# W5500.net
KiCad netlist of a schematic drawn in Altium Designer
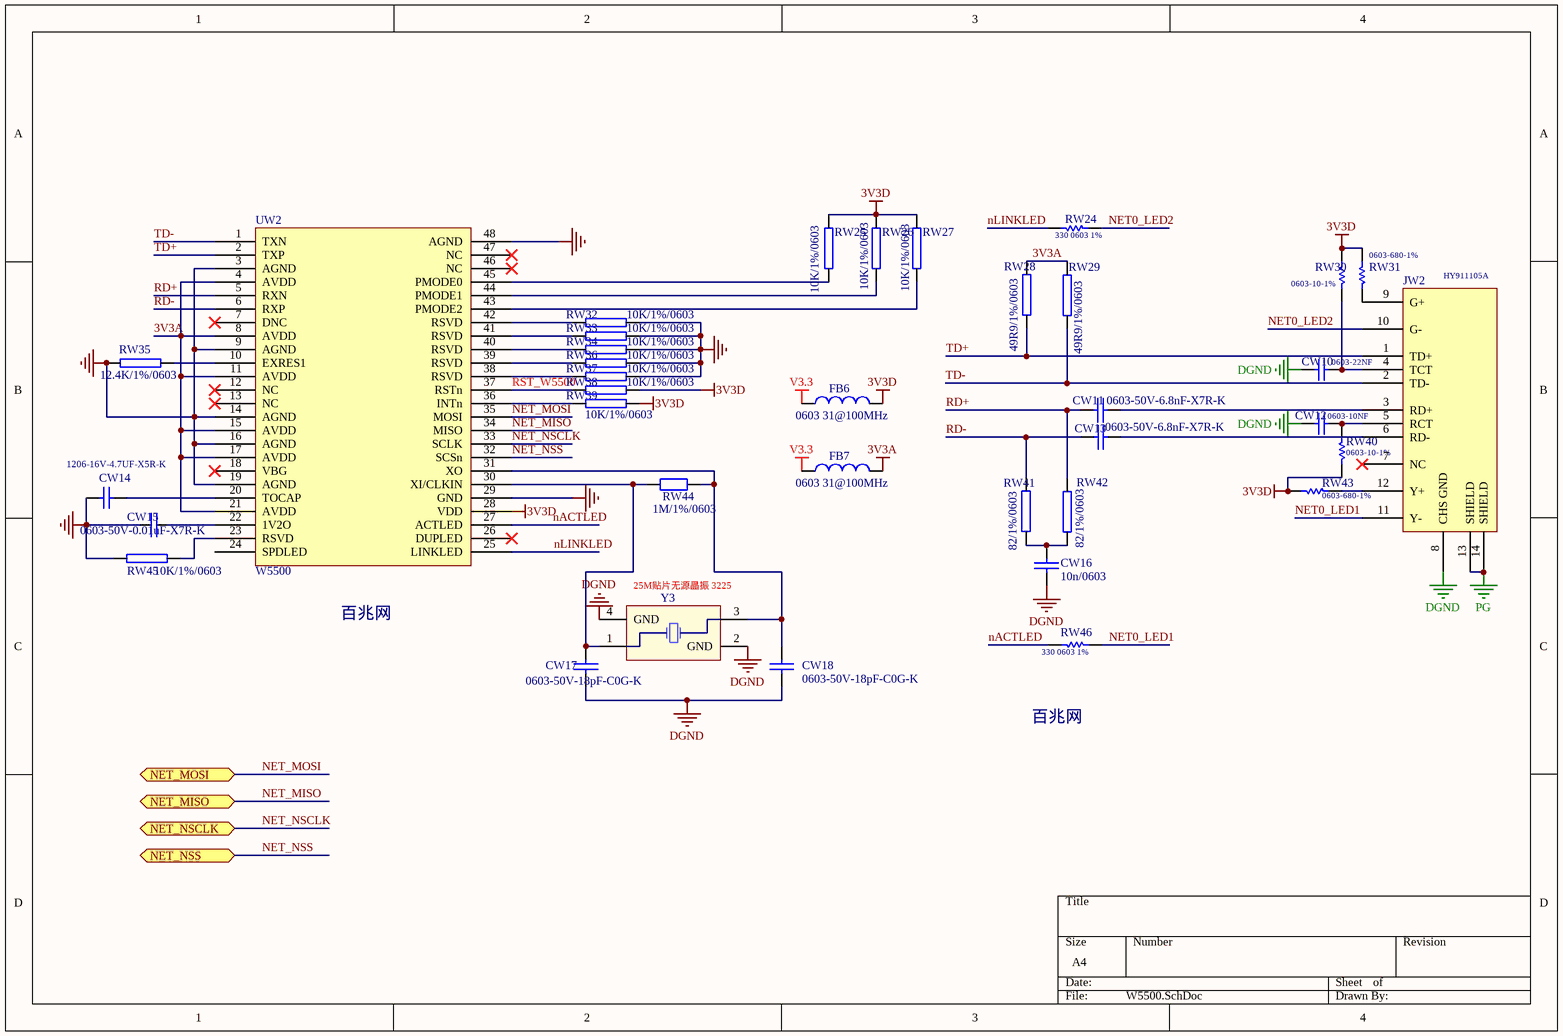
[diagram p0: W5500.SchDoc]

(export (version "E")
  (design (tool "Eeschema 10.0.6"))
  (components
    (comp (ref "CW10")
      (value "0603-22NF")
      (footprint "0603C")
      (description "Capacitor")
      (fields (field (name "PUBLISHER") "Altium Limited"))
      (libsource (lib "Miscellaneous Devices") (part "Cap"))
    )
    (comp (ref "CW11")
      (value "0603-50V-6.8nF-X7R-K")
      (footprint "0603C")
      (description "Capacitor")
      (libsource (lib "*") (part "CAP"))
    )
    (comp (ref "CW12")
      (value "0603-10NF")
      (footprint "0603C")
      (description "Capacitor")
      (fields (field (name "PUBLISHER") "Altium Limited"))
      (libsource (lib "Miscellaneous Devices") (part "Cap"))
    )
    (comp (ref "CW13")
      (value "0603-50V-6.8nF-X7R-K")
      (footprint "0603C")
      (description "Capacitor")
      (libsource (lib "*") (part "CAP"))
    )
    (comp (ref "CW14")
      (value "1206-16V-4.7UF-X5R-K")
      (footprint "1206C")
      (description "贴片电容")
      (fields (field (name "PUBLISHER") "Altium Limited"))
      (libsource (lib "Miscellaneous Devices") (part "Cap"))
    )
    (comp (ref "CW15")
      (value "0603-50V-0.01uF-X7R-K")
      (footprint "0603C")
      (description "Capacitor")
      (libsource (lib "SCH-QQ") (part "CAP"))
    )
    (comp (ref "CW16")
      (value "10n/0603")
      (footprint "0603C")
      (description "Capacitor")
      (libsource (lib "*") (part "CAP"))
    )
    (comp (ref "CW17")
      (value "0603-50V-18pF-C0G-K")
      (footprint "0603C")
      (description "Capacitor")
      (libsource (lib "*") (part "CAP"))
    )
    (comp (ref "CW18")
      (value "0603-50V-18pF-C0G-K")
      (footprint "0603C")
      (description "Capacitor")
      (libsource (lib "*") (part "CAP"))
    )
    (comp (ref "FB6")
      (value "0603 31@100MHz")
      (footprint "0603L")
      (description "Inductor")
      (fields (field (name "PUBLISHER") "Altium Limited"))
      (libsource (lib "Miscellaneous Devices") (part "Inductor"))
    )
    (comp (ref "FB7")
      (value "0603 31@100MHz")
      (footprint "0603L")
      (description "Inductor")
      (fields (field (name "PUBLISHER") "Altium Limited"))
      (libsource (lib "Miscellaneous Devices") (part "Inductor"))
    )
    (comp (ref "JW2")
      (value "HY911105A")
      (footprint "HY911105A")
      (libsource (lib "SCH-QQ") (part "HY911105A"))
    )
    (comp (ref "RW24")
      (value "330 0603 1%")
      (footprint "0603R")
      (description "Resistor")
      (fields (field (name "PUBLISHER") "Altium Limited"))
      (libsource (lib "Miscellaneous Devices") (part "Res1"))
    )
    (comp (ref "RW25") (value "10K/1%/0603") (footprint "0603R") (libsource (lib "SCH-QQ") (part "RES1")))
    (comp (ref "RW26") (value "10K/1%/0603") (footprint "0603R") (libsource (lib "SCH-QQ") (part "RES1")))
    (comp (ref "RW27") (value "10K/1%/0603") (footprint "0603R") (libsource (lib "SCH-QQ") (part "RES1")))
    (comp (ref "RW28") (value "49R9/1%/0603") (footprint "0603R") (libsource (lib "SCH-QQ") (part "RES1")))
    (comp (ref "RW29") (value "49R9/1%/0603") (footprint "0603R") (libsource (lib "SCH-QQ") (part "RES1")))
    (comp (ref "RW30")
      (value "0603-10-1%")
      (footprint "0603R")
      (description "Resistor")
      (fields (field (name "PUBLISHER") "Altium Limited"))
      (libsource (lib "Miscellaneous Devices") (part "Res1"))
    )
    (comp (ref "RW31")
      (value "0603-680-1%")
      (footprint "0603R")
      (description "Resistor")
      (fields (field (name "PUBLISHER") "Altium Limited"))
      (libsource (lib "Miscellaneous Devices") (part "Res1"))
    )
    (comp (ref "RW32") (value "10K/1%/0603") (footprint "0603R") (libsource (lib "SCH-QQ") (part "RES1")))
    (comp (ref "RW33") (value "10K/1%/0603") (footprint "0603R") (libsource (lib "SCH-QQ") (part "RES1")))
    (comp (ref "RW34") (value "10K/1%/0603") (footprint "0603R") (libsource (lib "SCH-QQ") (part "RES1")))
    (comp (ref "RW35") (value "12.4K/1%/0603") (footprint "0603R") (libsource (lib "SCH-QQ") (part "RES1")))
    (comp (ref "RW36") (value "10K/1%/0603") (footprint "0603R") (libsource (lib "SCH-QQ") (part "RES1")))
    (comp (ref "RW37") (value "10K/1%/0603") (footprint "0603R") (libsource (lib "SCH-QQ") (part "RES1")))
    (comp (ref "RW38") (value "10K/1%/0603") (footprint "0603R") (libsource (lib "SCH-QQ") (part "RES1")))
    (comp (ref "RW39") (value "10K/1%/0603") (footprint "0603R") (libsource (lib "SCH-QQ") (part "RES1")))
    (comp (ref "RW40")
      (value "0603-10-1%")
      (footprint "0603R")
      (description "Resistor")
      (fields (field (name "PUBLISHER") "Altium Limited"))
      (libsource (lib "Miscellaneous Devices") (part "Res1"))
    )
    (comp (ref "RW41") (value "82/1%/0603") (footprint "0603R") (libsource (lib "SCH-QQ") (part "RES1")))
    (comp (ref "RW42") (value "82/1%/0603") (footprint "0603R") (libsource (lib "SCH-QQ") (part "RES1")))
    (comp (ref "RW43")
      (value "0603-680-1%")
      (footprint "0603R")
      (description "Resistor")
      (fields (field (name "PUBLISHER") "Altium Limited"))
      (libsource (lib "Miscellaneous Devices") (part "Res1"))
    )
    (comp (ref "RW44")
      (value "1M/1%/0603")
      (footprint "0603R")
      (description "Resistor")
      (fields (field (name "PUBLISHER") "Altium Limited"))
      (libsource (lib "Miscellaneous Devices") (part "Res2"))
    )
    (comp (ref "RW45") (value "10K/1%/0603") (footprint "0603R") (libsource (lib "SCH-QQ") (part "RES1")))
    (comp (ref "RW46")
      (value "330 0603 1%")
      (footprint "0603R")
      (description "Resistor")
      (fields (field (name "PUBLISHER") "Altium Limited"))
      (libsource (lib "Miscellaneous Devices") (part "Res1"))
    )
    (comp (ref "UW2") (value "W5500") (footprint "LQFP-48") (libsource (lib "SCH-QQ") (part "W5500")))
    (comp (ref "Y3")
      (value "25M贴片无源晶振 3225")
      (footprint "OSC3225_4P")
      (description "Crystal Oscillator")
      (fields (field (name "PUBLISHER") "Altium Limited"))
      (libsource (lib "MCU_LPC1778") (part "OSC5032"))
    )
  )
  (nets
    (net (code "1") (name "/NET0_LED1") (class "Default")
      (node (ref "JW2") (pin "11") (pinfunction "Y-_11") (pintype "passive"))
      (node (ref "RW46") (pin "1") (pinfunction "1_1") (pintype "passive"))
    )
    (net (code "2") (name "/NET0_LED2") (class "Default")
      (node (ref "JW2") (pin "10") (pinfunction "G-_10") (pintype "passive"))
      (node (ref "RW24") (pin "1") (pinfunction "1_1") (pintype "passive"))
    )
    (net (code "3") (name "/NET_MISO") (class "Default")
      (node (ref "UW2") (pin "34") (pinfunction "MISO_34") (pintype "passive"))
    )
    (net (code "4") (name "/NET_MOSI") (class "Default")
      (node (ref "UW2") (pin "35") (pinfunction "MOSI_35") (pintype "passive"))
    )
    (net (code "5") (name "/NET_NSCLK") (class "Default")
      (node (ref "UW2") (pin "33") (pinfunction "SCLK_33") (pintype "passive"))
    )
    (net (code "6") (name "/NET_NSS") (class "Default")
      (node (ref "UW2") (pin "32") (pinfunction "SCSn_32") (pintype "passive"))
    )
    (net (code "7") (name "/RD+") (class "Default")
      (node (ref "CW11") (pin "2") (pinfunction "2_2") (pintype "passive"))
      (node (ref "RW42") (pin "2") (pintype "passive"))
      (node (ref "UW2") (pin "5") (pinfunction "RXN_5") (pintype "passive"))
    )
    (net (code "8") (name "/RD-") (class "Default")
      (node (ref "CW13") (pin "2") (pinfunction "2_2") (pintype "passive"))
      (node (ref "RW41") (pin "2") (pintype "passive"))
      (node (ref "UW2") (pin "6") (pinfunction "RXP_6") (pintype "passive"))
    )
    (net (code "9") (name "/RST_W5500") (class "Default")
      (node (ref "RW38") (pin "1") (pintype "passive"))
      (node (ref "UW2") (pin "37") (pinfunction "RSTn_37") (pintype "passive"))
    )
    (net (code "10") (name "/TD+") (class "Default")
      (node (ref "JW2") (pin "1") (pinfunction "TD+_1") (pintype "passive"))
      (node (ref "RW28") (pin "1") (pintype "passive"))
      (node (ref "UW2") (pin "2") (pinfunction "TXP_2") (pintype "passive"))
    )
    (net (code "11") (name "/TD-") (class "Default")
      (node (ref "JW2") (pin "2") (pinfunction "TD-_2") (pintype "passive"))
      (node (ref "RW29") (pin "1") (pintype "passive"))
      (node (ref "UW2") (pin "1") (pinfunction "TXN_1") (pintype "passive"))
    )
    (net (code "12") (name "/nACTLED") (class "Default")
      (node (ref "RW46") (pin "2") (pinfunction "2_2") (pintype "passive"))
      (node (ref "UW2") (pin "27") (pinfunction "ACTLED_27") (pintype "passive"))
    )
    (net (code "13") (name "/nLINKLED") (class "Default")
      (node (ref "RW24") (pin "2") (pinfunction "2_2") (pintype "passive"))
      (node (ref "UW2") (pin "25") (pinfunction "LINKLED_25") (pintype "passive"))
    )
    (net (code "14") (name "3V3A") (class "Default")
      (node (ref "FB7") (pin "2") (pinfunction "2_2") (pintype "passive"))
      (node (ref "RW28") (pin "2") (pintype "passive"))
      (node (ref "RW29") (pin "2") (pintype "passive"))
      (node (ref "UW2") (pin "11") (pinfunction "AVDD_11") (pintype "passive"))
      (node (ref "UW2") (pin "15") (pinfunction "AVDD_15") (pintype "passive"))
      (node (ref "UW2") (pin "17") (pinfunction "AVDD_17") (pintype "passive"))
      (node (ref "UW2") (pin "21") (pinfunction "AVDD_21") (pintype "passive"))
      (node (ref "UW2") (pin "4") (pinfunction "AVDD_4") (pintype "passive"))
      (node (ref "UW2") (pin "8") (pinfunction "AVDD_8") (pintype "passive"))
    )
    (net (code "15") (name "3V3D") (class "Default")
      (node (ref "FB6") (pin "2") (pinfunction "2_2") (pintype "passive"))
      (node (ref "RW25") (pin "2") (pintype "passive"))
      (node (ref "RW26") (pin "2") (pintype "passive"))
      (node (ref "RW27") (pin "2") (pintype "passive"))
      (node (ref "RW30") (pin "1") (pinfunction "1_1") (pintype "passive"))
      (node (ref "RW31") (pin "1") (pinfunction "1_1") (pintype "passive"))
      (node (ref "RW38") (pin "2") (pintype "passive"))
      (node (ref "RW39") (pin "2") (pintype "passive"))
      (node (ref "RW40") (pin "1") (pinfunction "1_1") (pintype "passive"))
      (node (ref "RW43") (pin "1") (pinfunction "1_1") (pintype "passive"))
      (node (ref "UW2") (pin "28") (pinfunction "VDD_28") (pintype "passive"))
    )
    (net (code "16") (name "DGND") (class "Default")
      (node (ref "CW10") (pin "2") (pinfunction "2_2") (pintype "passive"))
      (node (ref "CW12") (pin "2") (pinfunction "2_2") (pintype "passive"))
      (node (ref "CW14") (pin "2") (pinfunction "2_2") (pintype "passive"))
      (node (ref "CW15") (pin "2") (pinfunction "2_2") (pintype "passive"))
      (node (ref "CW16") (pin "2") (pinfunction "2_2") (pintype "passive"))
      (node (ref "CW17") (pin "1") (pinfunction "1_1") (pintype "passive"))
      (node (ref "CW18") (pin "1") (pinfunction "1_1") (pintype "passive"))
      (node (ref "JW2") (pin "8") (pinfunction "CHS_GND_8") (pintype "passive"))
      (node (ref "RW32") (pin "1") (pintype "passive"))
      (node (ref "RW33") (pin "1") (pintype "passive"))
      (node (ref "RW34") (pin "1") (pintype "passive"))
      (node (ref "RW35") (pin "2") (pintype "passive"))
      (node (ref "RW36") (pin "1") (pintype "passive"))
      (node (ref "RW37") (pin "1") (pintype "passive"))
      (node (ref "RW45") (pin "2") (pintype "passive"))
      (node (ref "UW2") (pin "14") (pinfunction "AGND_14") (pintype "passive"))
      (node (ref "UW2") (pin "16") (pinfunction "AGND_16") (pintype "passive"))
      (node (ref "UW2") (pin "19") (pinfunction "AGND_19") (pintype "passive"))
      (node (ref "UW2") (pin "29") (pinfunction "GND_29") (pintype "passive"))
      (node (ref "UW2") (pin "3") (pinfunction "AGND_3") (pintype "passive"))
      (node (ref "UW2") (pin "48") (pinfunction "AGND_48") (pintype "passive"))
      (node (ref "UW2") (pin "9") (pinfunction "AGND_9") (pintype "passive"))
      (node (ref "Y3") (pin "2") (pinfunction "GND_2") (pintype "passive"))
      (node (ref "Y3") (pin "4") (pinfunction "GND_4") (pintype "passive"))
    )
    (net (code "17") (name "Net-(CW16-Pad1)") (class "Default")
      (node (ref "CW16") (pin "1") (pinfunction "1_1") (pintype "passive"))
      (node (ref "RW41") (pin "1") (pintype "passive"))
      (node (ref "RW42") (pin "1") (pintype "passive"))
    )
    (net (code "18") (name "Net-(JW2-G+)") (class "Default")
      (node (ref "JW2") (pin "9") (pinfunction "G+_9") (pintype "passive"))
      (node (ref "RW31") (pin "2") (pinfunction "2_2") (pintype "passive"))
    )
    (net (code "19") (name "Net-(JW2-RCT)") (class "Default")
      (node (ref "CW12") (pin "1") (pinfunction "1_1") (pintype "passive"))
      (node (ref "JW2") (pin "5") (pinfunction "RCT_5") (pintype "passive"))
      (node (ref "RW40") (pin "2") (pinfunction "2_2") (pintype "passive"))
    )
    (net (code "20") (name "Net-(JW2-RD+)") (class "Default")
      (node (ref "CW11") (pin "1") (pinfunction "1_1") (pintype "passive"))
      (node (ref "JW2") (pin "3") (pinfunction "RD+_3") (pintype "passive"))
    )
    (net (code "21") (name "Net-(JW2-RD-)") (class "Default")
      (node (ref "CW13") (pin "1") (pinfunction "1_1") (pintype "passive"))
      (node (ref "JW2") (pin "6") (pinfunction "RD-_6") (pintype "passive"))
    )
    (net (code "22") (name "Net-(JW2-TCT)") (class "Default")
      (node (ref "CW10") (pin "1") (pinfunction "1_1") (pintype "passive"))
      (node (ref "JW2") (pin "4") (pinfunction "TCT_4") (pintype "passive"))
      (node (ref "RW30") (pin "2") (pinfunction "2_2") (pintype "passive"))
    )
    (net (code "23") (name "Net-(JW2-Y+)") (class "Default")
      (node (ref "JW2") (pin "12") (pinfunction "Y+_12") (pintype "passive"))
      (node (ref "RW43") (pin "2") (pinfunction "2_2") (pintype "passive"))
    )
    (net (code "24") (name "Net-(RW32-Pad2)") (class "Default")
      (node (ref "RW32") (pin "2") (pintype "passive"))
      (node (ref "UW2") (pin "42") (pinfunction "RSVD_42") (pintype "passive"))
    )
    (net (code "25") (name "Net-(RW33-Pad2)") (class "Default")
      (node (ref "RW33") (pin "2") (pintype "passive"))
      (node (ref "UW2") (pin "41") (pinfunction "RSVD_41") (pintype "passive"))
    )
    (net (code "26") (name "Net-(RW34-Pad2)") (class "Default")
      (node (ref "RW34") (pin "2") (pintype "passive"))
      (node (ref "UW2") (pin "40") (pinfunction "RSVD_40") (pintype "passive"))
    )
    (net (code "27") (name "Net-(RW36-Pad2)") (class "Default")
      (node (ref "RW36") (pin "2") (pintype "passive"))
      (node (ref "UW2") (pin "39") (pinfunction "RSVD_39") (pintype "passive"))
    )
    (net (code "28") (name "Net-(RW37-Pad2)") (class "Default")
      (node (ref "RW37") (pin "2") (pintype "passive"))
      (node (ref "UW2") (pin "38") (pinfunction "RSVD_38") (pintype "passive"))
    )
    (net (code "29") (name "Net-(RW45-Pad1)") (class "Default")
      (node (ref "RW45") (pin "1") (pintype "passive"))
      (node (ref "UW2") (pin "23") (pinfunction "RSVD_23") (pintype "passive"))
    )
    (net (code "30") (name "Net-(UW2-1V2O)") (class "Default")
      (node (ref "CW15") (pin "1") (pinfunction "1_1") (pintype "passive"))
      (node (ref "UW2") (pin "22") (pinfunction "1V2O_22") (pintype "passive"))
    )
    (net (code "31") (name "Net-(UW2-EXRES1)") (class "Default")
      (node (ref "RW35") (pin "1") (pintype "passive"))
      (node (ref "UW2") (pin "10") (pinfunction "EXRES1_10") (pintype "passive"))
    )
    (net (code "32") (name "Net-(UW2-INTn)") (class "Default")
      (node (ref "RW39") (pin "1") (pintype "passive"))
      (node (ref "UW2") (pin "36") (pinfunction "INTn_36") (pintype "passive"))
    )
    (net (code "33") (name "Net-(UW2-PMODE0)") (class "Default")
      (node (ref "RW25") (pin "1") (pintype "passive"))
      (node (ref "UW2") (pin "45") (pinfunction "PMODE0_45") (pintype "passive"))
    )
    (net (code "34") (name "Net-(UW2-PMODE1)") (class "Default")
      (node (ref "RW26") (pin "1") (pintype "passive"))
      (node (ref "UW2") (pin "44") (pinfunction "PMODE1_44") (pintype "passive"))
    )
    (net (code "35") (name "Net-(UW2-PMODE2)") (class "Default")
      (node (ref "RW27") (pin "1") (pintype "passive"))
      (node (ref "UW2") (pin "43") (pinfunction "PMODE2_43") (pintype "passive"))
    )
    (net (code "36") (name "Net-(UW2-TOCAP)") (class "Default")
      (node (ref "CW14") (pin "1") (pinfunction "1_1") (pintype "passive"))
      (node (ref "UW2") (pin "20") (pinfunction "TOCAP_20") (pintype "passive"))
    )
    (net (code "37") (name "Net-(UW2-XI{slash}CLKIN)") (class "Default")
      (node (ref "CW17") (pin "2") (pinfunction "2_2") (pintype "passive"))
      (node (ref "RW44") (pin "2") (pinfunction "2_2") (pintype "passive"))
      (node (ref "UW2") (pin "30") (pinfunction "XI/CLKIN_30") (pintype "passive"))
      (node (ref "Y3") (pin "1") (pinfunction "OSC1_1") (pintype "passive"))
    )
    (net (code "38") (name "Net-(UW2-XO)") (class "Default")
      (node (ref "CW18") (pin "2") (pinfunction "2_2") (pintype "passive"))
      (node (ref "RW44") (pin "1") (pinfunction "1_1") (pintype "passive"))
      (node (ref "UW2") (pin "31") (pinfunction "XO_31") (pintype "passive"))
      (node (ref "Y3") (pin "3") (pinfunction "3_3") (pintype "passive"))
    )
    (net (code "39") (name "PG") (class "Default")
      (node (ref "JW2") (pin "13") (pinfunction "SHIELD_13") (pintype "passive"))
      (node (ref "JW2") (pin "14") (pinfunction "SHIELD_14") (pintype "passive"))
    )
    (net (code "40") (name "V3.3") (class "Default")
      (node (ref "FB6") (pin "1") (pinfunction "1_1") (pintype "passive"))
      (node (ref "FB7") (pin "1") (pinfunction "1_1") (pintype "passive"))
    )
    (net (code "41") (name "unconnected-(JW2-NC-Pad7)") (class "Default")
      (node (ref "JW2") (pin "7") (pinfunction "NC_7") (pintype "passive+no_connect"))
    )
    (net (code "42") (name "unconnected-(UW2-DNC-Pad7)") (class "Default")
      (node (ref "UW2") (pin "7") (pinfunction "DNC_7") (pintype "passive+no_connect"))
    )
    (net (code "43") (name "unconnected-(UW2-DUPLED-Pad26)") (class "Default")
      (node (ref "UW2") (pin "26") (pinfunction "DUPLED_26") (pintype "passive+no_connect"))
    )
    (net (code "44") (name "unconnected-(UW2-NC-Pad12)") (class "Default")
      (node (ref "UW2") (pin "12") (pinfunction "NC_12") (pintype "passive+no_connect"))
    )
    (net (code "45") (name "unconnected-(UW2-NC-Pad13)") (class "Default")
      (node (ref "UW2") (pin "13") (pinfunction "NC_13") (pintype "passive+no_connect"))
    )
    (net (code "46") (name "unconnected-(UW2-NC-Pad46)") (class "Default")
      (node (ref "UW2") (pin "46") (pinfunction "NC_46") (pintype "passive+no_connect"))
    )
    (net (code "47") (name "unconnected-(UW2-NC-Pad47)") (class "Default")
      (node (ref "UW2") (pin "47") (pinfunction "NC_47") (pintype "passive+no_connect"))
    )
    (net (code "48") (name "unconnected-(UW2-SPDLED-Pad24)") (class "Default")
      (node (ref "UW2") (pin "24") (pinfunction "SPDLED_24") (pintype "passive"))
    )
    (net (code "49") (name "unconnected-(UW2-VBG-Pad18)") (class "Default")
      (node (ref "UW2") (pin "18") (pinfunction "VBG_18") (pintype "passive+no_connect"))
    )
  )
)
